# STM32L486_Test.net
KiCad netlist of a schematic drawn in EAGLE
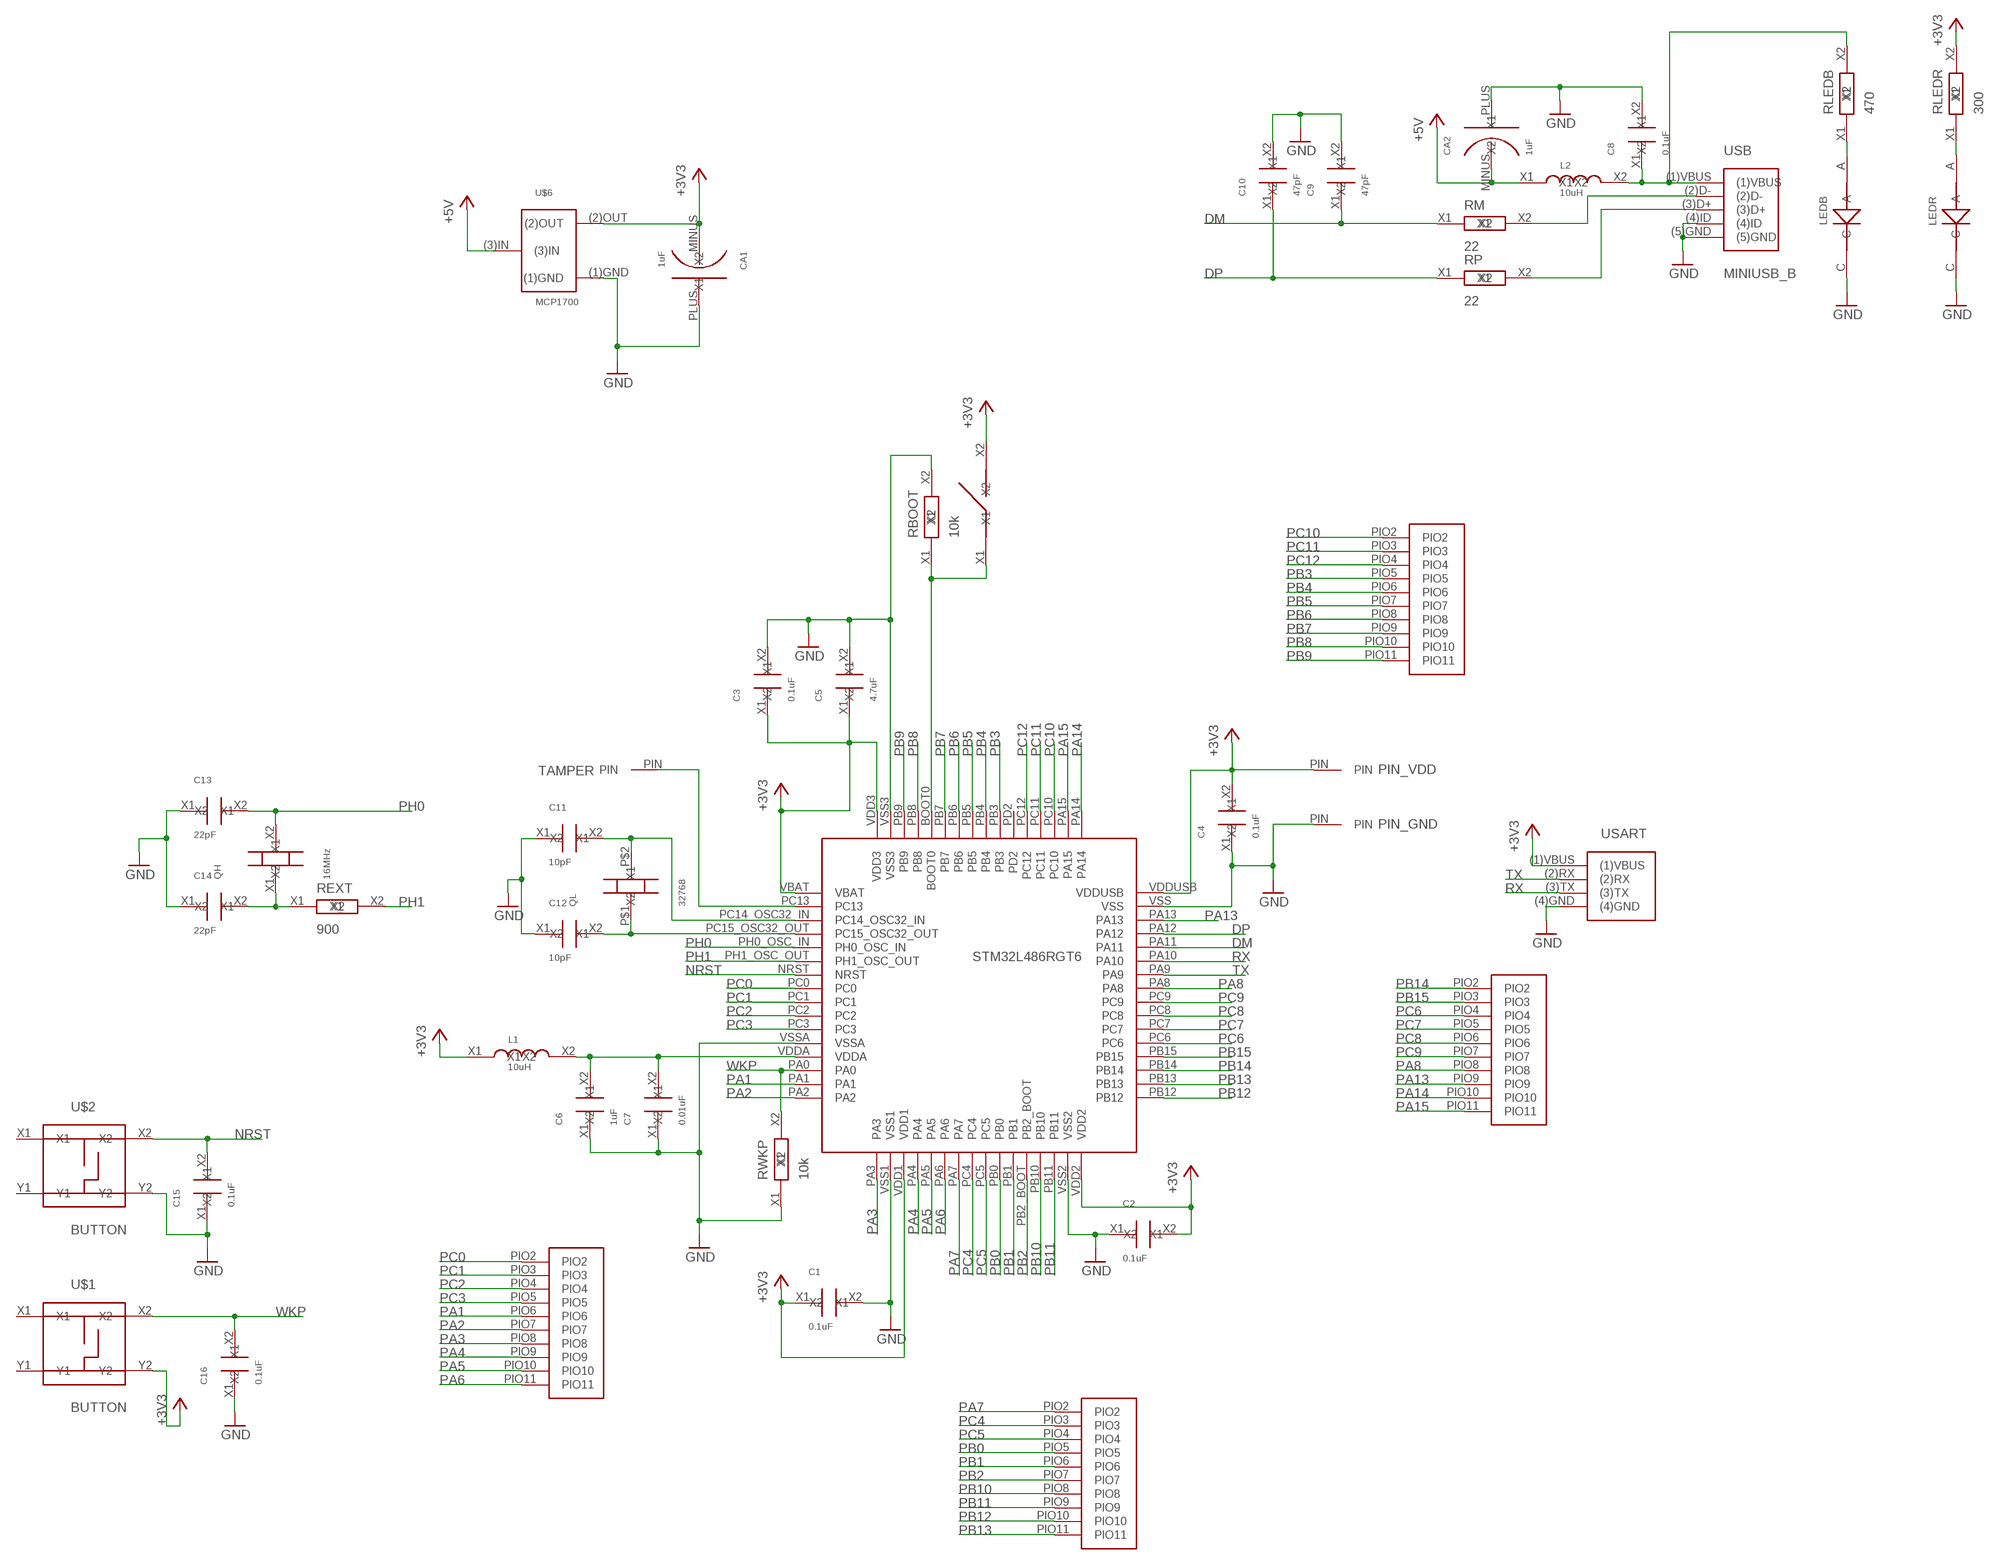
[diagram p0: schematic, sheet 1]

(export (version "E")
  (design (tool "Eeschema 10.0.6"))
  (components
    (comp (ref "C1")
      (value "0.1uF")
      (footprint "eagle-import:SMD_2.1X1.25")
      (libsource (lib "eagle-import") (part "C_SMD_2.1X1.25"))
    )
    (comp (ref "C2")
      (value "0.1uF")
      (footprint "eagle-import:SMD_2.1X1.25")
      (libsource (lib "eagle-import") (part "C_SMD_2.1X1.25"))
    )
    (comp (ref "C3")
      (value "0.1uF")
      (footprint "eagle-import:SMD_2.1X1.25")
      (libsource (lib "eagle-import") (part "C_SMD_2.1X1.25"))
    )
    (comp (ref "C4")
      (value "0.1uF")
      (footprint "eagle-import:SMD_2.1X1.25")
      (libsource (lib "eagle-import") (part "C_SMD_2.1X1.25"))
    )
    (comp (ref "C5")
      (value "4.7uF")
      (footprint "eagle-import:SMD_2.1X1.25")
      (libsource (lib "eagle-import") (part "C_SMD_2.1X1.25"))
    )
    (comp (ref "C6")
      (value "1uF")
      (footprint "eagle-import:SMD_2.1X1.25")
      (libsource (lib "eagle-import") (part "C_SMD_2.1X1.25"))
    )
    (comp (ref "C7")
      (value "0.01uF")
      (footprint "eagle-import:SMD_2.1X1.25")
      (libsource (lib "eagle-import") (part "C_SMD_2.1X1.25"))
    )
    (comp (ref "C8")
      (value "0.1uF")
      (footprint "eagle-import:SMD_2.1X1.25")
      (libsource (lib "eagle-import") (part "C_SMD_2.1X1.25"))
    )
    (comp (ref "C9")
      (value "47pF")
      (footprint "eagle-import:SMD_2.1X1.25")
      (libsource (lib "eagle-import") (part "C_SMD_2.1X1.25"))
    )
    (comp (ref "C10")
      (value "47pF")
      (footprint "eagle-import:SMD_2.1X1.25")
      (libsource (lib "eagle-import") (part "C_SMD_2.1X1.25"))
    )
    (comp (ref "C11")
      (value "10pF")
      (footprint "eagle-import:SMD_2.1X1.25")
      (libsource (lib "eagle-import") (part "C_SMD_2.1X1.25"))
    )
    (comp (ref "C12")
      (value "10pF")
      (footprint "eagle-import:SMD_2.1X1.25")
      (libsource (lib "eagle-import") (part "C_SMD_2.1X1.25"))
    )
    (comp (ref "C13")
      (value "22pF")
      (footprint "eagle-import:SMD_2.1X1.25")
      (libsource (lib "eagle-import") (part "C_SMD_2.1X1.25"))
    )
    (comp (ref "C14")
      (value "22pF")
      (footprint "eagle-import:SMD_2.1X1.25")
      (libsource (lib "eagle-import") (part "C_SMD_2.1X1.25"))
    )
    (comp (ref "C15")
      (value "0.1uF")
      (footprint "eagle-import:SMD_2.1X1.25")
      (libsource (lib "eagle-import") (part "C_SMD_2.1X1.25"))
    )
    (comp (ref "C16")
      (value "0.1uF")
      (footprint "eagle-import:SMD_2.1X1.25")
      (libsource (lib "eagle-import") (part "C_SMD_2.1X1.25"))
    )
    (comp (ref "CA1")
      (value "1uF")
      (footprint "eagle-import:C_SMD_TA_A")
      (libsource (lib "eagle-import") (part "C_SMD_TA_A"))
    )
    (comp (ref "CA2")
      (value "1uF")
      (footprint "eagle-import:C_SMD_TA_A")
      (libsource (lib "eagle-import") (part "C_SMD_TA_A"))
    )
    (comp (ref "L1")
      (value "10uH")
      (footprint "eagle-import:SMD_2.1X1.25")
      (libsource (lib "eagle-import") (part "L_SMD_2.1X1.25"))
    )
    (comp (ref "L2")
      (value "10uH")
      (footprint "eagle-import:SMD_2.1X1.25")
      (libsource (lib "eagle-import") (part "L_SMD_2.1X1.25"))
    )
    (comp (ref "LEDB")
      (value "LED0805")
      (footprint "eagle-import:SMD0805")
      (libsource (lib "eagle-import") (part "LED0805"))
    )
    (comp (ref "LEDR")
      (value "LED0805")
      (footprint "eagle-import:SMD0805")
      (libsource (lib "eagle-import") (part "LED0805"))
    )
    (comp (ref "PIN_GND")
      (value "PIN")
      (footprint "eagle-import:PIN")
      (libsource (lib "eagle-import") (part "PIN"))
    )
    (comp (ref "PIN_VDD")
      (value "PIN")
      (footprint "eagle-import:PIN")
      (libsource (lib "eagle-import") (part "PIN"))
    )
    (comp (ref "QH")
      (value "16MHz")
      (footprint "eagle-import:QUARTZ_SMD")
      (libsource (lib "eagle-import") (part "QUARTZ_SMD"))
    )
    (comp (ref "QL")
      (value "32768")
      (footprint "eagle-import:QUARTZ_CYL")
      (libsource (lib "eagle-import") (part "QUARTZ_CYL"))
    )
    (comp (ref "RBOOT")
      (value "10k")
      (footprint "eagle-import:SMD_2.1X1.25")
      (libsource (lib "eagle-import") (part "R_SMD_2.1X1.25"))
    )
    (comp (ref "REXT")
      (value "900")
      (footprint "eagle-import:SMD_2.1X1.25")
      (libsource (lib "eagle-import") (part "R_SMD_2.1X1.25"))
    )
    (comp (ref "RLEDB")
      (value "470")
      (footprint "eagle-import:SMD_2.1X1.25")
      (libsource (lib "eagle-import") (part "R_SMD_2.1X1.25"))
    )
    (comp (ref "RLEDR")
      (value "300")
      (footprint "eagle-import:SMD_2.1X1.25")
      (libsource (lib "eagle-import") (part "R_SMD_2.1X1.25"))
    )
    (comp (ref "RM")
      (value "22")
      (footprint "eagle-import:SMD_2.1X1.25")
      (libsource (lib "eagle-import") (part "R_SMD_2.1X1.25"))
    )
    (comp (ref "RP")
      (value "22")
      (footprint "eagle-import:SMD_2.1X1.25")
      (libsource (lib "eagle-import") (part "R_SMD_2.1X1.25"))
    )
    (comp (ref "RWKP")
      (value "10k")
      (footprint "eagle-import:SMD_2.1X1.25")
      (libsource (lib "eagle-import") (part "R_SMD_2.1X1.25"))
    )
    (comp (ref "STM32L486RGT6")
      (value "STM32L486")
      (footprint "eagle-import:STM32L486")
      (libsource (lib "eagle-import") (part "STM32L486"))
    )
    (comp (ref "TAMPER")
      (value "PIN")
      (footprint "eagle-import:PIN")
      (libsource (lib "eagle-import") (part "PIN"))
    )
    (comp (ref "U$1")
      (value "BUTTON")
      (footprint "eagle-import:BUTTON")
      (libsource (lib "eagle-import") (part "BUTTON"))
    )
    (comp (ref "U$2")
      (value "BUTTON")
      (footprint "eagle-import:BUTTON")
      (libsource (lib "eagle-import") (part "BUTTON"))
    )
    (comp (ref "U$3")
      (value "PIO_10")
      (footprint "eagle-import:PIO_10")
      (libsource (lib "eagle-import") (part "PIO_10"))
    )
    (comp (ref "U$4")
      (value "PIO_10")
      (footprint "eagle-import:PIO_10")
      (libsource (lib "eagle-import") (part "PIO_10"))
    )
    (comp (ref "U$5")
      (value "PIO_10")
      (footprint "eagle-import:PIO_10")
      (libsource (lib "eagle-import") (part "PIO_10"))
    )
    (comp (ref "U$6")
      (value "MCP1700")
      (footprint "eagle-import:MCP1700")
      (libsource (lib "eagle-import") (part "MCP1700"))
    )
    (comp (ref "U$7")
      (value "PIO_10")
      (footprint "eagle-import:PIO_10")
      (libsource (lib "eagle-import") (part "PIO_10"))
    )
    (comp (ref "U$9")
      (value "DIP_1")
      (footprint "eagle-import:DIP_1")
      (libsource (lib "eagle-import") (part "DIP_1"))
    )
    (comp (ref "USART")
      (value "USART")
      (footprint "eagle-import:USART")
      (libsource (lib "eagle-import") (part "USART"))
    )
    (comp (ref "USB")
      (value "MINIUSB_B")
      (footprint "eagle-import:MINIUSB_B")
      (libsource (lib "eagle-import") (part "MINIUSB_B"))
    )
  )
  (nets
    (net (code "1") (name "+3V3") (class "Default")
      (node (ref "C1") (pin "X1") (pinfunction "X1_X1") (pintype "bidirectional"))
      (node (ref "C2") (pin "X2") (pinfunction "X2_X2") (pintype "bidirectional"))
      (node (ref "C3") (pin "X1") (pinfunction "X1_X1") (pintype "bidirectional"))
      (node (ref "C4") (pin "X2") (pinfunction "X2_X2") (pintype "bidirectional"))
      (node (ref "C5") (pin "X1") (pinfunction "X1_X1") (pintype "bidirectional"))
      (node (ref "CA1") (pin "MINUS") (pinfunction "X1_MINUS") (pintype "bidirectional"))
      (node (ref "L1") (pin "X1") (pinfunction "X1_X1") (pintype "bidirectional"))
      (node (ref "PIN_VDD") (pin "PIN") (pinfunction "PIN_PIN") (pintype "bidirectional"))
      (node (ref "RLEDR") (pin "X2") (pinfunction "X2_X2") (pintype "bidirectional"))
      (node (ref "STM32L486RGT6") (pin "VBAT") (pinfunction "VBAT_VBAT") (pintype "bidirectional"))
      (node (ref "STM32L486RGT6") (pin "VDD1") (pinfunction "VDD1_VDD1") (pintype "bidirectional"))
      (node (ref "STM32L486RGT6") (pin "VDD2") (pinfunction "VDD2_VDD2") (pintype "bidirectional"))
      (node (ref "STM32L486RGT6") (pin "VDD3") (pinfunction "VDD3_VDD3") (pintype "bidirectional"))
      (node (ref "STM32L486RGT6") (pin "VDDUSB") (pinfunction "VDDUSB_VDDUSB") (pintype "bidirectional"))
      (node (ref "U$1") (pin "Y2") (pinfunction "Y2_Y2") (pintype "bidirectional"))
      (node (ref "U$6") (pin "(2)OUT") (pinfunction "(2)OUT_(2)OUT") (pintype "bidirectional"))
      (node (ref "U$9") (pin "X2") (pinfunction "X2_X2") (pintype "bidirectional"))
      (node (ref "USART") (pin "(1)VBUS") (pinfunction "(1)VBUS_(1)VBUS") (pintype "bidirectional"))
    )
    (net (code "2") (name "+5V") (class "Default")
      (node (ref "CA2") (pin "MINUS") (pinfunction "X1_MINUS") (pintype "bidirectional"))
      (node (ref "L2") (pin "X1") (pinfunction "X1_X1") (pintype "bidirectional"))
      (node (ref "U$6") (pin "(3)IN") (pinfunction "(3)IN_(3)IN") (pintype "bidirectional"))
    )
    (net (code "3") (name "/DM") (class "Default")
      (node (ref "C9") (pin "X1") (pinfunction "X1_X1") (pintype "bidirectional"))
      (node (ref "RM") (pin "X1") (pinfunction "X1_X1") (pintype "bidirectional"))
      (node (ref "STM32L486RGT6") (pin "PA11") (pinfunction "PA11_PA11") (pintype "bidirectional"))
    )
    (net (code "4") (name "/DP") (class "Default")
      (node (ref "C10") (pin "X1") (pinfunction "X1_X1") (pintype "bidirectional"))
      (node (ref "RP") (pin "X1") (pinfunction "X1_X1") (pintype "bidirectional"))
      (node (ref "STM32L486RGT6") (pin "PA12") (pinfunction "PA12_PA12") (pintype "bidirectional"))
    )
    (net (code "5") (name "/NRST") (class "Default")
      (node (ref "C15") (pin "X2") (pinfunction "X2_X2") (pintype "bidirectional"))
      (node (ref "STM32L486RGT6") (pin "NRST") (pinfunction "NRST_NRST") (pintype "bidirectional"))
      (node (ref "U$2") (pin "X2") (pinfunction "X2_X2") (pintype "bidirectional"))
    )
    (net (code "6") (name "/PA1") (class "Default")
      (node (ref "STM32L486RGT6") (pin "PA1") (pinfunction "PA1_PA1") (pintype "bidirectional"))
      (node (ref "U$3") (pin "PIO6") (pinfunction "PIO6_PIO6") (pintype "bidirectional"))
    )
    (net (code "7") (name "/PA2") (class "Default")
      (node (ref "STM32L486RGT6") (pin "PA2") (pinfunction "PA2_PA2") (pintype "bidirectional"))
      (node (ref "U$3") (pin "PIO7") (pinfunction "PIO7_PIO7") (pintype "bidirectional"))
    )
    (net (code "8") (name "/PA3") (class "Default")
      (node (ref "STM32L486RGT6") (pin "PA3") (pinfunction "PA3_PA3") (pintype "bidirectional"))
      (node (ref "U$3") (pin "PIO8") (pinfunction "PIO8_PIO8") (pintype "bidirectional"))
    )
    (net (code "9") (name "/PA4") (class "Default")
      (node (ref "STM32L486RGT6") (pin "PA4") (pinfunction "PA4_PA4") (pintype "bidirectional"))
      (node (ref "U$3") (pin "PIO9") (pinfunction "PIO9_PIO9") (pintype "bidirectional"))
    )
    (net (code "10") (name "/PA5") (class "Default")
      (node (ref "STM32L486RGT6") (pin "PA5") (pinfunction "PA5_PA5") (pintype "bidirectional"))
      (node (ref "U$3") (pin "PIO10") (pinfunction "PIO10_PIO10") (pintype "bidirectional"))
    )
    (net (code "11") (name "/PA6") (class "Default")
      (node (ref "STM32L486RGT6") (pin "PA6") (pinfunction "PA6_PA6") (pintype "bidirectional"))
      (node (ref "U$3") (pin "PIO11") (pinfunction "PIO11_PIO11") (pintype "bidirectional"))
    )
    (net (code "12") (name "/PA7") (class "Default")
      (node (ref "STM32L486RGT6") (pin "PA7") (pinfunction "PA7_PA7") (pintype "bidirectional"))
      (node (ref "U$4") (pin "PIO2") (pinfunction "PIO2_PIO2") (pintype "bidirectional"))
    )
    (net (code "13") (name "/PA8") (class "Default")
      (node (ref "STM32L486RGT6") (pin "PA8") (pinfunction "PA8_PA8") (pintype "bidirectional"))
      (node (ref "U$5") (pin "PIO8") (pinfunction "PIO8_PIO8") (pintype "bidirectional"))
    )
    (net (code "14") (name "/PA13") (class "Default")
      (node (ref "STM32L486RGT6") (pin "PA13") (pinfunction "PA13_PA13") (pintype "bidirectional"))
      (node (ref "U$5") (pin "PIO9") (pinfunction "PIO9_PIO9") (pintype "bidirectional"))
    )
    (net (code "15") (name "/PA14") (class "Default")
      (node (ref "STM32L486RGT6") (pin "PA14") (pinfunction "PA14_PA14") (pintype "bidirectional"))
      (node (ref "U$5") (pin "PIO10") (pinfunction "PIO10_PIO10") (pintype "bidirectional"))
    )
    (net (code "16") (name "/PA15") (class "Default")
      (node (ref "STM32L486RGT6") (pin "PA15") (pinfunction "PA15_PA15") (pintype "bidirectional"))
      (node (ref "U$5") (pin "PIO11") (pinfunction "PIO11_PIO11") (pintype "bidirectional"))
    )
    (net (code "17") (name "/PB0") (class "Default")
      (node (ref "STM32L486RGT6") (pin "PB0") (pinfunction "PB0_PB0") (pintype "bidirectional"))
      (node (ref "U$4") (pin "PIO5") (pinfunction "PIO5_PIO5") (pintype "bidirectional"))
    )
    (net (code "18") (name "/PB1") (class "Default")
      (node (ref "STM32L486RGT6") (pin "PB1") (pinfunction "PB1_PB1") (pintype "bidirectional"))
      (node (ref "U$4") (pin "PIO6") (pinfunction "PIO6_PIO6") (pintype "bidirectional"))
    )
    (net (code "19") (name "/PB2") (class "Default")
      (node (ref "STM32L486RGT6") (pin "PB2_BOOT") (pinfunction "PB2_BOOT_PB2_BOOT") (pintype "bidirectional"))
      (node (ref "U$4") (pin "PIO7") (pinfunction "PIO7_PIO7") (pintype "bidirectional"))
    )
    (net (code "20") (name "/PB3") (class "Default")
      (node (ref "STM32L486RGT6") (pin "PB3") (pinfunction "PB3_PB3") (pintype "bidirectional"))
      (node (ref "U$7") (pin "PIO5") (pinfunction "PIO5_PIO5") (pintype "bidirectional"))
    )
    (net (code "21") (name "/PB4") (class "Default")
      (node (ref "STM32L486RGT6") (pin "PB4") (pinfunction "PB4_PB4") (pintype "bidirectional"))
      (node (ref "U$7") (pin "PIO6") (pinfunction "PIO6_PIO6") (pintype "bidirectional"))
    )
    (net (code "22") (name "/PB5") (class "Default")
      (node (ref "STM32L486RGT6") (pin "PB5") (pinfunction "PB5_PB5") (pintype "bidirectional"))
      (node (ref "U$7") (pin "PIO7") (pinfunction "PIO7_PIO7") (pintype "bidirectional"))
    )
    (net (code "23") (name "/PB6") (class "Default")
      (node (ref "STM32L486RGT6") (pin "PB6") (pinfunction "PB6_PB6") (pintype "bidirectional"))
      (node (ref "U$7") (pin "PIO8") (pinfunction "PIO8_PIO8") (pintype "bidirectional"))
    )
    (net (code "24") (name "/PB7") (class "Default")
      (node (ref "STM32L486RGT6") (pin "PB7") (pinfunction "PB7_PB7") (pintype "bidirectional"))
      (node (ref "U$7") (pin "PIO9") (pinfunction "PIO9_PIO9") (pintype "bidirectional"))
    )
    (net (code "25") (name "/PB8") (class "Default")
      (node (ref "STM32L486RGT6") (pin "PB8") (pinfunction "PB8_PB8") (pintype "bidirectional"))
      (node (ref "U$7") (pin "PIO10") (pinfunction "PIO10_PIO10") (pintype "bidirectional"))
    )
    (net (code "26") (name "/PB9") (class "Default")
      (node (ref "STM32L486RGT6") (pin "PB9") (pinfunction "PB9_PB9") (pintype "bidirectional"))
      (node (ref "U$7") (pin "PIO11") (pinfunction "PIO11_PIO11") (pintype "bidirectional"))
    )
    (net (code "27") (name "/PB10") (class "Default")
      (node (ref "STM32L486RGT6") (pin "PB10") (pinfunction "PB10_PB10") (pintype "bidirectional"))
      (node (ref "U$4") (pin "PIO8") (pinfunction "PIO8_PIO8") (pintype "bidirectional"))
    )
    (net (code "28") (name "/PB11") (class "Default")
      (node (ref "STM32L486RGT6") (pin "PB11") (pinfunction "PB11_PB11") (pintype "bidirectional"))
      (node (ref "U$4") (pin "PIO9") (pinfunction "PIO9_PIO9") (pintype "bidirectional"))
    )
    (net (code "29") (name "/PB12") (class "Default")
      (node (ref "STM32L486RGT6") (pin "PB12") (pinfunction "PB12_PB12") (pintype "bidirectional"))
      (node (ref "U$4") (pin "PIO10") (pinfunction "PIO10_PIO10") (pintype "bidirectional"))
    )
    (net (code "30") (name "/PB13") (class "Default")
      (node (ref "STM32L486RGT6") (pin "PB13") (pinfunction "PB13_PB13") (pintype "bidirectional"))
      (node (ref "U$4") (pin "PIO11") (pinfunction "PIO11_PIO11") (pintype "bidirectional"))
    )
    (net (code "31") (name "/PB14") (class "Default")
      (node (ref "STM32L486RGT6") (pin "PB14") (pinfunction "PB14_PB14") (pintype "bidirectional"))
      (node (ref "U$5") (pin "PIO2") (pinfunction "PIO2_PIO2") (pintype "bidirectional"))
    )
    (net (code "32") (name "/PB15") (class "Default")
      (node (ref "STM32L486RGT6") (pin "PB15") (pinfunction "PB15_PB15") (pintype "bidirectional"))
      (node (ref "U$5") (pin "PIO3") (pinfunction "PIO3_PIO3") (pintype "bidirectional"))
    )
    (net (code "33") (name "/PC0") (class "Default")
      (node (ref "STM32L486RGT6") (pin "PC0") (pinfunction "PC0_PC0") (pintype "bidirectional"))
      (node (ref "U$3") (pin "PIO2") (pinfunction "PIO2_PIO2") (pintype "bidirectional"))
    )
    (net (code "34") (name "/PC1") (class "Default")
      (node (ref "STM32L486RGT6") (pin "PC1") (pinfunction "PC1_PC1") (pintype "bidirectional"))
      (node (ref "U$3") (pin "PIO3") (pinfunction "PIO3_PIO3") (pintype "bidirectional"))
    )
    (net (code "35") (name "/PC2") (class "Default")
      (node (ref "STM32L486RGT6") (pin "PC2") (pinfunction "PC2_PC2") (pintype "bidirectional"))
      (node (ref "U$3") (pin "PIO4") (pinfunction "PIO4_PIO4") (pintype "bidirectional"))
    )
    (net (code "36") (name "/PC3") (class "Default")
      (node (ref "STM32L486RGT6") (pin "PC3") (pinfunction "PC3_PC3") (pintype "bidirectional"))
      (node (ref "U$3") (pin "PIO5") (pinfunction "PIO5_PIO5") (pintype "bidirectional"))
    )
    (net (code "37") (name "/PC4") (class "Default")
      (node (ref "STM32L486RGT6") (pin "PC4") (pinfunction "PC4_PC4") (pintype "bidirectional"))
      (node (ref "U$4") (pin "PIO3") (pinfunction "PIO3_PIO3") (pintype "bidirectional"))
    )
    (net (code "38") (name "/PC5") (class "Default")
      (node (ref "STM32L486RGT6") (pin "PC5") (pinfunction "PC5_PC5") (pintype "bidirectional"))
      (node (ref "U$4") (pin "PIO4") (pinfunction "PIO4_PIO4") (pintype "bidirectional"))
    )
    (net (code "39") (name "/PC6") (class "Default")
      (node (ref "STM32L486RGT6") (pin "PC6") (pinfunction "PC6_PC6") (pintype "bidirectional"))
      (node (ref "U$5") (pin "PIO4") (pinfunction "PIO4_PIO4") (pintype "bidirectional"))
    )
    (net (code "40") (name "/PC7") (class "Default")
      (node (ref "STM32L486RGT6") (pin "PC7") (pinfunction "PC7_PC7") (pintype "bidirectional"))
      (node (ref "U$5") (pin "PIO5") (pinfunction "PIO5_PIO5") (pintype "bidirectional"))
    )
    (net (code "41") (name "/PC8") (class "Default")
      (node (ref "STM32L486RGT6") (pin "PC8") (pinfunction "PC8_PC8") (pintype "bidirectional"))
      (node (ref "U$5") (pin "PIO6") (pinfunction "PIO6_PIO6") (pintype "bidirectional"))
    )
    (net (code "42") (name "/PC9") (class "Default")
      (node (ref "STM32L486RGT6") (pin "PC9") (pinfunction "PC9_PC9") (pintype "bidirectional"))
      (node (ref "U$5") (pin "PIO7") (pinfunction "PIO7_PIO7") (pintype "bidirectional"))
    )
    (net (code "43") (name "/PC10") (class "Default")
      (node (ref "STM32L486RGT6") (pin "PC10") (pinfunction "PC10_PC10") (pintype "bidirectional"))
      (node (ref "U$7") (pin "PIO2") (pinfunction "PIO2_PIO2") (pintype "bidirectional"))
    )
    (net (code "44") (name "/PC11") (class "Default")
      (node (ref "STM32L486RGT6") (pin "PC11") (pinfunction "PC11_PC11") (pintype "bidirectional"))
      (node (ref "U$7") (pin "PIO3") (pinfunction "PIO3_PIO3") (pintype "bidirectional"))
    )
    (net (code "45") (name "/PC12") (class "Default")
      (node (ref "STM32L486RGT6") (pin "PC12") (pinfunction "PC12_PC12") (pintype "bidirectional"))
      (node (ref "U$7") (pin "PIO4") (pinfunction "PIO4_PIO4") (pintype "bidirectional"))
    )
    (net (code "46") (name "/PH0") (class "Default")
      (node (ref "C13") (pin "X2") (pinfunction "X2_X2") (pintype "bidirectional"))
      (node (ref "QH") (pin "X2") (pinfunction "X2_X2") (pintype "bidirectional"))
      (node (ref "STM32L486RGT6") (pin "PH0_OSC_IN") (pinfunction "PH0_OSC_IN_PH0_OSC_IN") (pintype "bidirectional"))
    )
    (net (code "47") (name "/PH1") (class "Default")
      (node (ref "REXT") (pin "X2") (pinfunction "X2_X2") (pintype "bidirectional"))
      (node (ref "STM32L486RGT6") (pin "PH1_OSC_OUT") (pinfunction "PH1_OSC_OUT_PH1_OSC_OUT") (pintype "bidirectional"))
    )
    (net (code "48") (name "/RX") (class "Default")
      (node (ref "STM32L486RGT6") (pin "PA10") (pinfunction "PA10_PA10") (pintype "bidirectional"))
      (node (ref "USART") (pin "(3)TX") (pinfunction "(3)TX_(3)TX") (pintype "bidirectional"))
    )
    (net (code "49") (name "/TX") (class "Default")
      (node (ref "STM32L486RGT6") (pin "PA9") (pinfunction "PA9_PA9") (pintype "bidirectional"))
      (node (ref "USART") (pin "(2)RX") (pinfunction "(2)RX_(2)RX") (pintype "bidirectional"))
    )
    (net (code "50") (name "/WKP") (class "Default")
      (node (ref "C16") (pin "X2") (pinfunction "X2_X2") (pintype "bidirectional"))
      (node (ref "RWKP") (pin "X2") (pinfunction "X2_X2") (pintype "bidirectional"))
      (node (ref "STM32L486RGT6") (pin "PA0") (pinfunction "PA0_PA0") (pintype "bidirectional"))
      (node (ref "U$1") (pin "X2") (pinfunction "X2_X2") (pintype "bidirectional"))
    )
    (net (code "51") (name "GND") (class "Default")
      (node (ref "C1") (pin "X2") (pinfunction "X2_X2") (pintype "bidirectional"))
      (node (ref "C10") (pin "X2") (pinfunction "X2_X2") (pintype "bidirectional"))
      (node (ref "C11") (pin "X1") (pinfunction "X1_X1") (pintype "bidirectional"))
      (node (ref "C12") (pin "X1") (pinfunction "X1_X1") (pintype "bidirectional"))
      (node (ref "C13") (pin "X1") (pinfunction "X1_X1") (pintype "bidirectional"))
      (node (ref "C14") (pin "X1") (pinfunction "X1_X1") (pintype "bidirectional"))
      (node (ref "C15") (pin "X1") (pinfunction "X1_X1") (pintype "bidirectional"))
      (node (ref "C16") (pin "X1") (pinfunction "X1_X1") (pintype "bidirectional"))
      (node (ref "C2") (pin "X1") (pinfunction "X1_X1") (pintype "bidirectional"))
      (node (ref "C3") (pin "X2") (pinfunction "X2_X2") (pintype "bidirectional"))
      (node (ref "C4") (pin "X1") (pinfunction "X1_X1") (pintype "bidirectional"))
      (node (ref "C5") (pin "X2") (pinfunction "X2_X2") (pintype "bidirectional"))
      (node (ref "C6") (pin "X1") (pinfunction "X1_X1") (pintype "bidirectional"))
      (node (ref "C7") (pin "X1") (pinfunction "X1_X1") (pintype "bidirectional"))
      (node (ref "C8") (pin "X2") (pinfunction "X2_X2") (pintype "bidirectional"))
      (node (ref "C9") (pin "X2") (pinfunction "X2_X2") (pintype "bidirectional"))
      (node (ref "CA1") (pin "PLUS") (pinfunction "X2_PLUS") (pintype "bidirectional"))
      (node (ref "CA2") (pin "PLUS") (pinfunction "X2_PLUS") (pintype "bidirectional"))
      (node (ref "LEDB") (pin "C") (pinfunction "C_C") (pintype "bidirectional"))
      (node (ref "LEDR") (pin "C") (pinfunction "C_C") (pintype "bidirectional"))
      (node (ref "PIN_GND") (pin "PIN") (pinfunction "PIN_PIN") (pintype "bidirectional"))
      (node (ref "RBOOT") (pin "X2") (pinfunction "X2_X2") (pintype "bidirectional"))
      (node (ref "RWKP") (pin "X1") (pinfunction "X1_X1") (pintype "bidirectional"))
      (node (ref "STM32L486RGT6") (pin "VSS") (pinfunction "VSS_VSS") (pintype "bidirectional"))
      (node (ref "STM32L486RGT6") (pin "VSS1") (pinfunction "VSS1_VSS1") (pintype "bidirectional"))
      (node (ref "STM32L486RGT6") (pin "VSS2") (pinfunction "VSS2_VSS2") (pintype "bidirectional"))
      (node (ref "STM32L486RGT6") (pin "VSS3") (pinfunction "VSS3_VSS3") (pintype "bidirectional"))
      (node (ref "STM32L486RGT6") (pin "VSSA") (pinfunction "VSSA_VSSA") (pintype "bidirectional"))
      (node (ref "U$2") (pin "Y2") (pinfunction "Y2_Y2") (pintype "bidirectional"))
      (node (ref "U$6") (pin "(1)GND") (pinfunction "(1)GND_(1)GND") (pintype "bidirectional"))
      (node (ref "USART") (pin "(4)GND") (pinfunction "(4)GND_(4)GND") (pintype "bidirectional"))
      (node (ref "USB") (pin "(4)ID") (pinfunction "(4)ID_(4)ID") (pintype "bidirectional"))
      (node (ref "USB") (pin "(5)GND") (pinfunction "(5)GND_(5)GND") (pintype "bidirectional"))
    )
    (net (code "52") (name "Net-(C6-PadX2)") (class "Default")
      (node (ref "C6") (pin "X2") (pinfunction "X2_X2") (pintype "bidirectional"))
      (node (ref "C7") (pin "X2") (pinfunction "X2_X2") (pintype "bidirectional"))
      (node (ref "L1") (pin "X2") (pinfunction "X2_X2") (pintype "bidirectional"))
      (node (ref "STM32L486RGT6") (pin "VDDA") (pinfunction "VDDA_VDDA") (pintype "bidirectional"))
    )
    (net (code "53") (name "Net-(C8-PadX1)") (class "Default")
      (node (ref "C8") (pin "X1") (pinfunction "X1_X1") (pintype "bidirectional"))
      (node (ref "L2") (pin "X2") (pinfunction "X2_X2") (pintype "bidirectional"))
      (node (ref "RLEDB") (pin "X2") (pinfunction "X2_X2") (pintype "bidirectional"))
      (node (ref "USB") (pin "(1)VBUS") (pinfunction "(1)VBUS_(1)VBUS") (pintype "bidirectional"))
    )
    (net (code "54") (name "Net-(C14-PadX2)") (class "Default")
      (node (ref "C14") (pin "X2") (pinfunction "X2_X2") (pintype "bidirectional"))
      (node (ref "QH") (pin "X1") (pinfunction "X1_X1") (pintype "bidirectional"))
      (node (ref "REXT") (pin "X1") (pinfunction "X1_X1") (pintype "bidirectional"))
    )
    (net (code "55") (name "Net-(LEDB-PadA)") (class "Default")
      (node (ref "LEDB") (pin "A") (pinfunction "A_A") (pintype "bidirectional"))
      (node (ref "RLEDB") (pin "X1") (pinfunction "X1_X1") (pintype "bidirectional"))
    )
    (net (code "56") (name "Net-(LEDR-PadA)") (class "Default")
      (node (ref "LEDR") (pin "A") (pinfunction "A_A") (pintype "bidirectional"))
      (node (ref "RLEDR") (pin "X1") (pinfunction "X1_X1") (pintype "bidirectional"))
    )
    (net (code "57") (name "Net-(QL-X1)") (class "Default")
      (node (ref "C12") (pin "X2") (pinfunction "X2_X2") (pintype "bidirectional"))
      (node (ref "QL") (pin "P$1") (pinfunction "X1_P$1") (pintype "bidirectional"))
      (node (ref "STM32L486RGT6") (pin "PC15_OSC32_OUT") (pinfunction "PC15_OSC32_OUT_PC15_OSC32_OUT") (pintype "bidirectional"))
    )
    (net (code "58") (name "Net-(QL-X2)") (class "Default")
      (node (ref "C11") (pin "X2") (pinfunction "X2_X2") (pintype "bidirectional"))
      (node (ref "QL") (pin "P$2") (pinfunction "X2_P$2") (pintype "bidirectional"))
      (node (ref "STM32L486RGT6") (pin "PC14_OSC32_IN") (pinfunction "PC14_OSC32_IN_PC14_OSC32_IN") (pintype "bidirectional"))
    )
    (net (code "59") (name "Net-(RBOOT-PadX1)") (class "Default")
      (node (ref "RBOOT") (pin "X1") (pinfunction "X1_X1") (pintype "bidirectional"))
      (node (ref "STM32L486RGT6") (pin "BOOT0") (pinfunction "BOOT0_BOOT0") (pintype "bidirectional"))
      (node (ref "U$9") (pin "X1") (pinfunction "X1_X1") (pintype "bidirectional"))
    )
    (net (code "60") (name "Net-(RM-PadX2)") (class "Default")
      (node (ref "RM") (pin "X2") (pinfunction "X2_X2") (pintype "bidirectional"))
      (node (ref "USB") (pin "(2)D-") (pinfunction "(2)D-_(2)D-") (pintype "bidirectional"))
    )
    (net (code "61") (name "Net-(RP-PadX2)") (class "Default")
      (node (ref "RP") (pin "X2") (pinfunction "X2_X2") (pintype "bidirectional"))
      (node (ref "USB") (pin "(3)D+") (pinfunction "(3)D+_(3)D+") (pintype "bidirectional"))
    )
    (net (code "62") (name "Net-(STM32L486RGT6-PadPC13)") (class "Default")
      (node (ref "STM32L486RGT6") (pin "PC13") (pinfunction "PC13_PC13") (pintype "bidirectional"))
      (node (ref "TAMPER") (pin "PIN") (pinfunction "PIN_PIN") (pintype "bidirectional"))
    )
    (net (code "63") (name "unconnected-(STM32L486RGT6-PadPD2)") (class "Default")
      (node (ref "STM32L486RGT6") (pin "PD2") (pinfunction "PD2_PD2") (pintype "bidirectional"))
    )
    (net (code "64") (name "unconnected-(U$1-PadX1)") (class "Default")
      (node (ref "U$1") (pin "X1") (pinfunction "X1_X1") (pintype "bidirectional"))
    )
    (net (code "65") (name "unconnected-(U$1-PadY1)") (class "Default")
      (node (ref "U$1") (pin "Y1") (pinfunction "Y1_Y1") (pintype "bidirectional"))
    )
    (net (code "66") (name "unconnected-(U$2-PadX1)") (class "Default")
      (node (ref "U$2") (pin "X1") (pinfunction "X1_X1") (pintype "bidirectional"))
    )
    (net (code "67") (name "unconnected-(U$2-PadY1)") (class "Default")
      (node (ref "U$2") (pin "Y1") (pinfunction "Y1_Y1") (pintype "bidirectional"))
    )
  )
)
